# SCH_ESP-RotaryCell-Main-Carrier-Rev-A1_R.net
KiCad netlist of a schematic drawn in EasyEDA
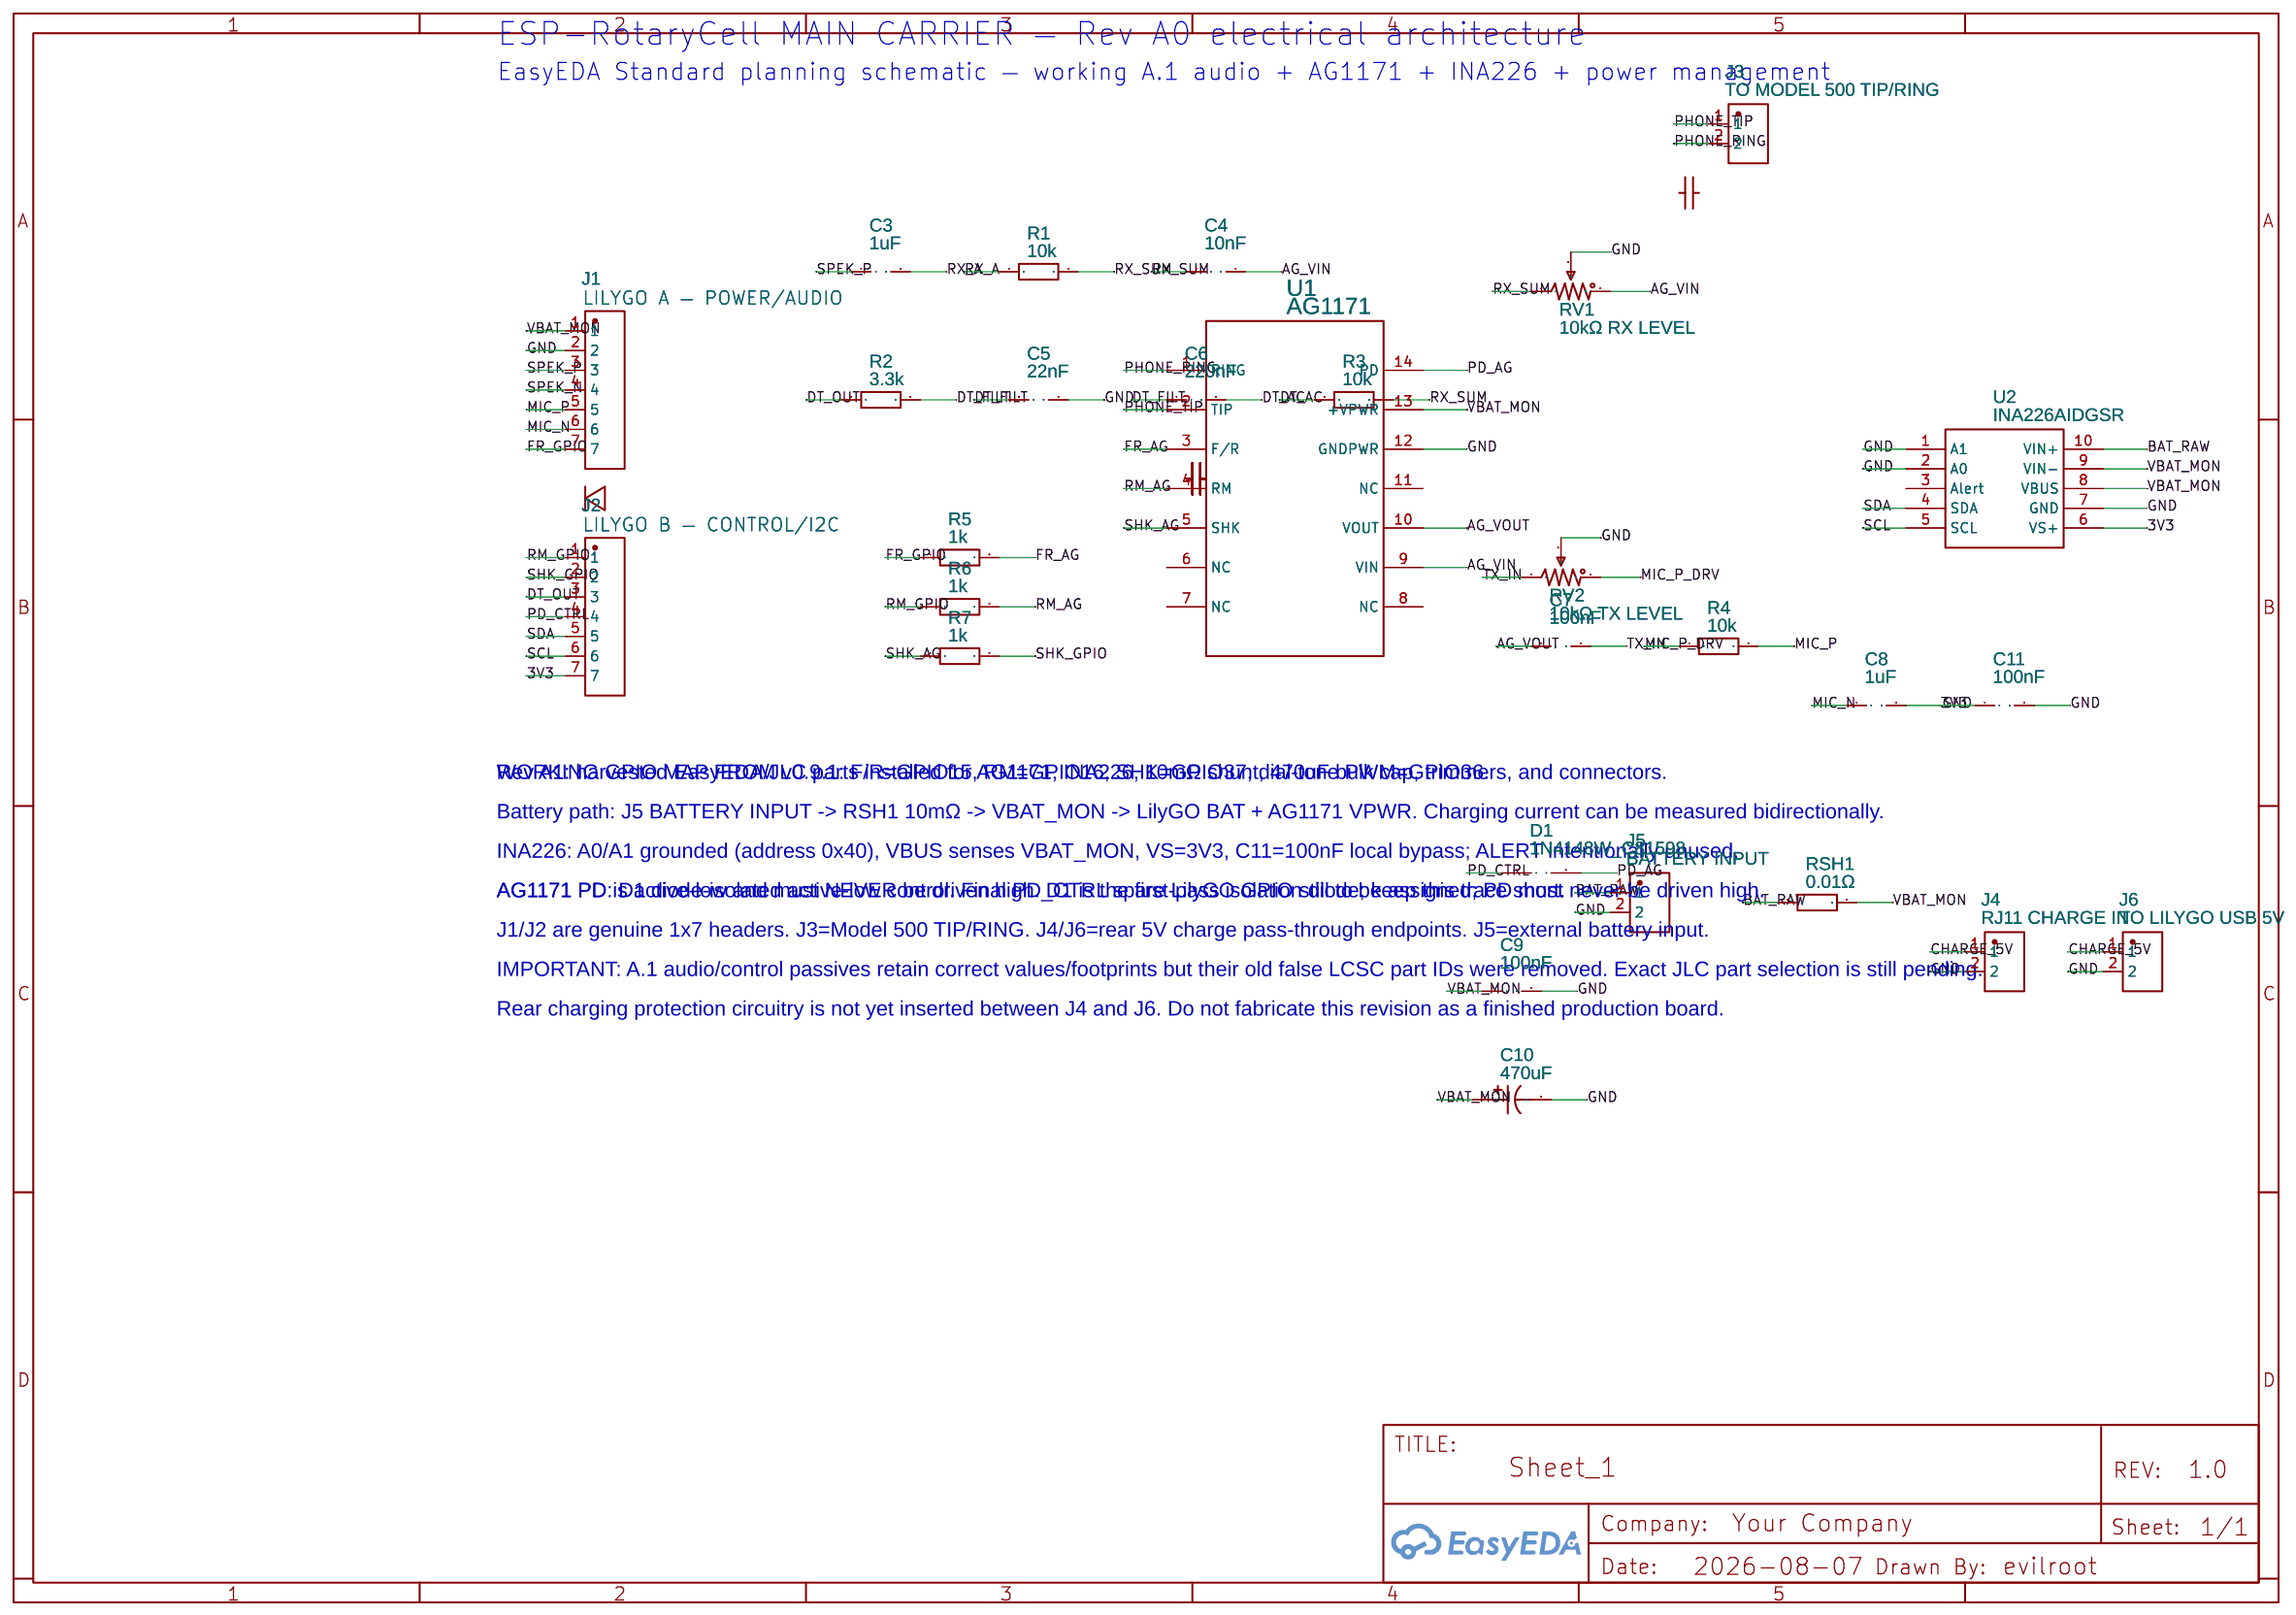
[diagram p0: Carrier_Rev_A1_RealParts]
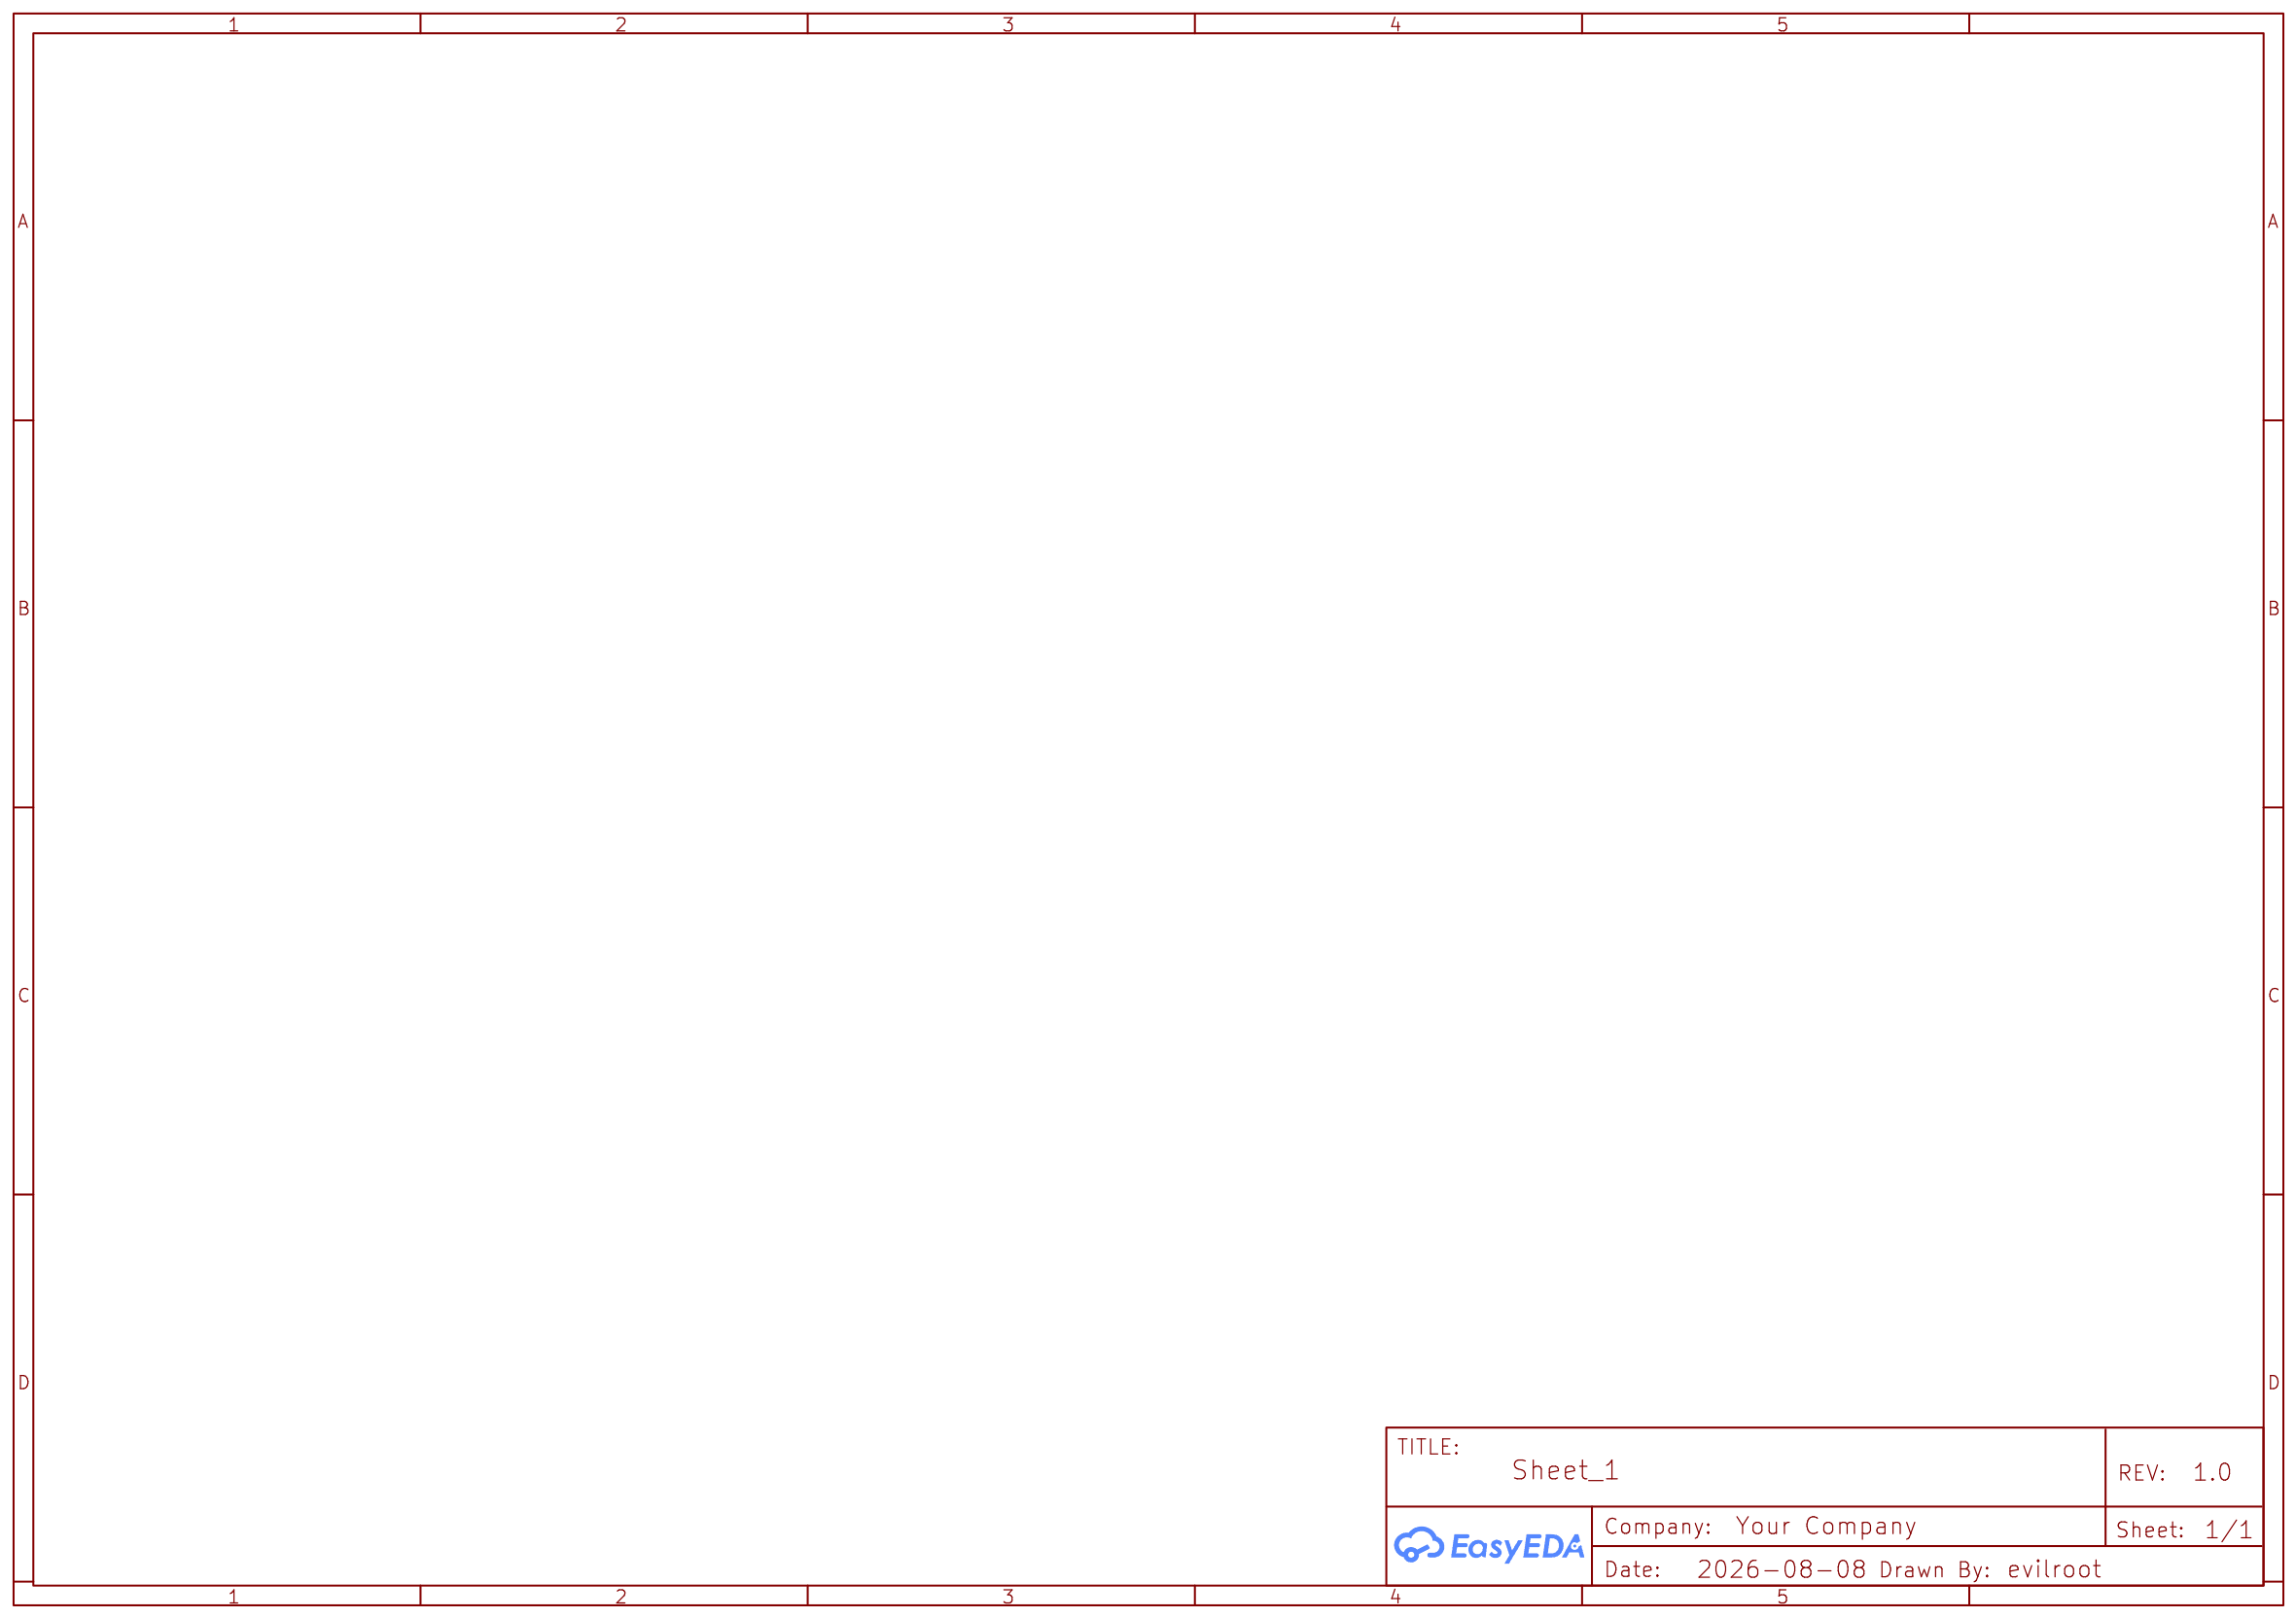
[diagram p1: Sheet_1]

(export (version "E")
  (design (tool "Eeschema 10.0.6"))
  (components
    (comp (ref "C3") (value "1uF") (libsource (lib "") (part "Unknown_440_-675")))
    (comp (ref "C4") (value "10nF") (libsource (lib "") (part "Unknown_610_-675")))
    (comp (ref "C5") (value "22nF") (libsource (lib "") (part "Unknown_520_-610")))
    (comp (ref "C6") (value "220nF") (libsource (lib "") (part "Unknown_600_-610")))
    (comp (ref "C7") (value "100nF") (libsource (lib "") (part "Unknown_785_-485")))
    (comp (ref "C8") (value "1uF") (libsource (lib "") (part "Unknown_945_-455")))
    (comp (ref "C9") (value "100nF") (libsource (lib "") (part "Unknown_760_-310")))
    (comp (ref "C10")
      (value "470uF")
      (fields
        (field (name "Manufacturer Part") "RYHT16V470UF5.5*11")
        (field (name "Manufacturer") "HONOR(荣誉)")
      )
      (libsource (lib "") (part "RYHT16V470UF5.5*11"))
    )
    (comp (ref "C11") (value "100nF") (libsource (lib "") (part "Unknown_1010_-455")))
    (comp (ref "D1")
      (value "1N4148W_C81598")
      (fields (field (name "Manufacturer Part") "1N4148W") (field (name "Manufacturer") "ST(先科)"))
      (libsource (lib "") (part "1N4148W_C81598"))
    )
    (comp (ref "J1")
      (value "LILYGO A — POWER/AUDIO")
      (fields
        (field (name "Manufacturer Part") "PM2.54-1x7PZZ-H8.5")
        (field (name "Manufacturer") "SHOU HAN(首韩)")
      )
      (libsource (lib "") (part "PM2.54-1X7PZZ-H8.5"))
    )
    (comp (ref "J2")
      (value "LILYGO B — CONTROL/I2C")
      (fields
        (field (name "Manufacturer Part") "PM2.54-1x7PZZ-H8.5")
        (field (name "Manufacturer") "SHOU HAN(首韩)")
      )
      (libsource (lib "") (part "PM2.54-1X7PZZ-H8.5"))
    )
    (comp (ref "J3")
      (value "TO MODEL 500 TIP/RING")
      (fields
        (field (name "Manufacturer Part") "HMT-2.54-1*2PM")
        (field (name "Manufacturer") "HMTCONN(华明通)")
      )
      (libsource (lib "") (part "HMT-2.54-1*2PM"))
    )
    (comp (ref "J4")
      (value "RJ11 CHARGE IN")
      (fields
        (field (name "Manufacturer Part") "HMT-2.54-1*2PM")
        (field (name "Manufacturer") "HMTCONN(华明通)")
      )
      (libsource (lib "") (part "HMT-2.54-1*2PM"))
    )
    (comp (ref "J5")
      (value "BATTERY INPUT")
      (fields
        (field (name "Manufacturer Part") "HMT-2.54-1*2PM")
        (field (name "Manufacturer") "HMTCONN(华明通)")
      )
      (libsource (lib "") (part "HMT-2.54-1*2PM"))
    )
    (comp (ref "J6")
      (value "TO LILYGO USB 5V")
      (fields
        (field (name "Manufacturer Part") "HMT-2.54-1*2PM")
        (field (name "Manufacturer") "HMTCONN(华明通)")
      )
      (libsource (lib "") (part "HMT-2.54-1*2PM"))
    )
    (comp (ref "R1") (value "10k") (libsource (lib "") (part "Unknown_520_-675")))
    (comp (ref "R2") (value "3.3k") (libsource (lib "") (part "Unknown_440_-610")))
    (comp (ref "R3") (value "10k") (libsource (lib "") (part "Unknown_680_-610")))
    (comp (ref "R4") (value "10k") (libsource (lib "") (part "Unknown_865_-485")))
    (comp (ref "R5") (value "1k") (libsource (lib "") (part "Unknown_480_-530")))
    (comp (ref "R6") (value "1k") (libsource (lib "") (part "Unknown_480_-505")))
    (comp (ref "R7") (value "1k") (libsource (lib "") (part "Unknown_480_-480")))
    (comp (ref "RSH1")
      (value "0.01Ω")
      (fields (field (name "Manufacturer Part") "MRF6432(2512)LR010JTS") (field (name "Manufacturer") "SUP"))
      (libsource (lib "") (part "MRF6432(2512)LR010JTS"))
    )
    (comp (ref "RV1")
      (value "10kΩ RX LEVEL")
      (fields (field (name "Manufacturer Part") "PS10KV50-103A3030") (field (name "Manufacturer") "Amphenol"))
      (libsource (lib "") (part "PS10KV50-103A3030"))
    )
    (comp (ref "RV2")
      (value "10kΩ TX LEVEL")
      (fields (field (name "Manufacturer Part") "PS10KV50-103A3030") (field (name "Manufacturer") "Amphenol"))
      (libsource (lib "") (part "PS10KV50-103A3030"))
    )
    (comp (ref "U1")
      (value "AG1171")
      (fields (field (name "Manufacturer Part") "Ag1171") (field (name "Manufacturer") "Silver Telecom"))
      (libsource (lib "") (part "AG1171"))
    )
    (comp (ref "U2")
      (value "INA226AIDGSR")
      (fields (field (name "Manufacturer") "TI(德州仪器)"))
      (libsource (lib "") (part "INA226AIDGSR"))
    )
  )
  (nets
    (net (code "1") (name "3V3") (class "Default")
      (node (ref "C10") (pin "2") (pinfunction "2_2") (pintype "input"))
      (node (ref "C11") (pin "1") (pinfunction "1_1") (pintype "input"))
      (node (ref "C11") (pin "2") (pinfunction "2_2") (pintype "input"))
      (node (ref "C5") (pin "2") (pinfunction "2_2") (pintype "input"))
      (node (ref "C8") (pin "2") (pinfunction "2_2") (pintype "input"))
      (node (ref "C9") (pin "2") (pinfunction "2_2") (pintype "input"))
      (node (ref "J1") (pin "2") (pinfunction "2_2") (pintype "unspecified"))
      (node (ref "J2") (pin "7") (pinfunction "7_7") (pintype "unspecified"))
      (node (ref "J4") (pin "2") (pinfunction "2_2") (pintype "unspecified"))
      (node (ref "J5") (pin "2") (pinfunction "2_2") (pintype "unspecified"))
      (node (ref "J6") (pin "2") (pinfunction "2_2") (pintype "unspecified"))
      (node (ref "RV1") (pin "3") (pinfunction "3_3") (pintype "unspecified"))
      (node (ref "RV2") (pin "3") (pinfunction "3_3") (pintype "unspecified"))
      (node (ref "U1") (pin "12") (pinfunction "GNDPWR_12") (pintype "unspecified"))
      (node (ref "U2") (pin "1") (pinfunction "A1_1") (pintype "unspecified"))
      (node (ref "U2") (pin "2") (pinfunction "A0_2") (pintype "unspecified"))
      (node (ref "U2") (pin "6") (pinfunction "VS+_6") (pintype "unspecified"))
      (node (ref "U2") (pin "7") (pinfunction "GND_7") (pintype "unspecified"))
    )
    (net (code "2") (name "AG_VIN") (class "Default")
      (node (ref "C4") (pin "2") (pinfunction "2_2") (pintype "input"))
      (node (ref "RV1") (pin "2") (pinfunction "2_2") (pintype "unspecified"))
      (node (ref "U1") (pin "9") (pinfunction "VIN_9") (pintype "unspecified"))
    )
    (net (code "3") (name "AG_VOUT") (class "Default")
      (node (ref "C7") (pin "1") (pinfunction "1_1") (pintype "input"))
      (node (ref "U1") (pin "10") (pinfunction "VOUT_10") (pintype "unspecified"))
    )
    (net (code "4") (name "BAT_RAW") (class "Default")
      (node (ref "J5") (pin "1") (pinfunction "1_1") (pintype "unspecified"))
      (node (ref "RSH1") (pin "1") (pinfunction "1_1") (pintype "input"))
      (node (ref "U2") (pin "10") (pinfunction "VIN+_10") (pintype "unspecified"))
    )
    (net (code "5") (name "CHARGE_5V") (class "Default")
      (node (ref "J4") (pin "1") (pinfunction "1_1") (pintype "unspecified"))
      (node (ref "J6") (pin "1") (pinfunction "1_1") (pintype "unspecified"))
    )
    (net (code "6") (name "DT_AC") (class "Default")
      (node (ref "C6") (pin "2") (pinfunction "2_2") (pintype "input"))
      (node (ref "R3") (pin "1") (pinfunction "1_1") (pintype "input"))
    )
    (net (code "7") (name "DT_FILT") (class "Default")
      (node (ref "C5") (pin "1") (pinfunction "1_1") (pintype "input"))
      (node (ref "C6") (pin "1") (pinfunction "1_1") (pintype "input"))
      (node (ref "R2") (pin "2") (pinfunction "2_2") (pintype "input"))
    )
    (net (code "8") (name "DT_OUT") (class "Default")
      (node (ref "J2") (pin "3") (pinfunction "3_3") (pintype "unspecified"))
      (node (ref "R2") (pin "1") (pinfunction "1_1") (pintype "input"))
    )
    (net (code "9") (name "FR_AG") (class "Default")
      (node (ref "R5") (pin "2") (pinfunction "2_2") (pintype "input"))
      (node (ref "U1") (pin "3") (pinfunction "F/R_3") (pintype "unspecified"))
    )
    (net (code "10") (name "FR_GPIO") (class "Default")
      (node (ref "J1") (pin "7") (pinfunction "7_7") (pintype "unspecified"))
      (node (ref "R5") (pin "1") (pinfunction "1_1") (pintype "input"))
    )
    (net (code "11") (name "MIC_N") (class "Default")
      (node (ref "C8") (pin "1") (pinfunction "1_1") (pintype "input"))
      (node (ref "J1") (pin "6") (pinfunction "6_6") (pintype "unspecified"))
    )
    (net (code "12") (name "MIC_P") (class "Default")
      (node (ref "J1") (pin "5") (pinfunction "5_5") (pintype "unspecified"))
      (node (ref "R4") (pin "2") (pinfunction "2_2") (pintype "input"))
    )
    (net (code "13") (name "MIC_P_DRV") (class "Default")
      (node (ref "R4") (pin "1") (pinfunction "1_1") (pintype "input"))
      (node (ref "RV2") (pin "2") (pinfunction "2_2") (pintype "unspecified"))
    )
    (net (code "14") (name "PD_AG") (class "Default")
      (node (ref "D1") (pin "2") (pinfunction "A_2") (pintype "unspecified"))
      (node (ref "U1") (pin "14") (pinfunction "PD_14") (pintype "unspecified"))
    )
    (net (code "15") (name "PD_CTRL") (class "Default")
      (node (ref "D1") (pin "1") (pinfunction "K_1") (pintype "unspecified"))
      (node (ref "J2") (pin "4") (pinfunction "4_4") (pintype "unspecified"))
    )
    (net (code "16") (name "PHONE_RING") (class "Default")
      (node (ref "J3") (pin "2") (pinfunction "2_2") (pintype "unspecified"))
      (node (ref "U1") (pin "1") (pinfunction "RING_1") (pintype "unspecified"))
    )
    (net (code "17") (name "PHONE_TIP") (class "Default")
      (node (ref "J3") (pin "1") (pinfunction "1_1") (pintype "unspecified"))
      (node (ref "U1") (pin "2") (pinfunction "TIP_2") (pintype "unspecified"))
    )
    (net (code "18") (name "RM_AG") (class "Default")
      (node (ref "R6") (pin "2") (pinfunction "2_2") (pintype "input"))
      (node (ref "U1") (pin "4") (pinfunction "RM_4") (pintype "unspecified"))
    )
    (net (code "19") (name "RM_GPIO") (class "Default")
      (node (ref "J2") (pin "1") (pinfunction "1_1") (pintype "unspecified"))
      (node (ref "R6") (pin "1") (pinfunction "1_1") (pintype "input"))
    )
    (net (code "20") (name "RX_A") (class "Default")
      (node (ref "C3") (pin "2") (pinfunction "2_2") (pintype "input"))
      (node (ref "R1") (pin "1") (pinfunction "1_1") (pintype "input"))
    )
    (net (code "21") (name "RX_SUM") (class "Default")
      (node (ref "C4") (pin "1") (pinfunction "1_1") (pintype "input"))
      (node (ref "R1") (pin "2") (pinfunction "2_2") (pintype "input"))
      (node (ref "R3") (pin "2") (pinfunction "2_2") (pintype "input"))
      (node (ref "RV1") (pin "1") (pinfunction "1_1") (pintype "unspecified"))
    )
    (net (code "22") (name "SCL") (class "Default")
      (node (ref "J2") (pin "6") (pinfunction "6_6") (pintype "unspecified"))
      (node (ref "U2") (pin "5") (pinfunction "SCL_5") (pintype "unspecified"))
    )
    (net (code "23") (name "SDA") (class "Default")
      (node (ref "J2") (pin "5") (pinfunction "5_5") (pintype "unspecified"))
      (node (ref "U2") (pin "4") (pinfunction "SDA_4") (pintype "unspecified"))
    )
    (net (code "24") (name "SHK_AG") (class "Default")
      (node (ref "R7") (pin "1") (pinfunction "1_1") (pintype "input"))
      (node (ref "U1") (pin "5") (pinfunction "SHK_5") (pintype "unspecified"))
    )
    (net (code "25") (name "SHK_GPIO") (class "Default")
      (node (ref "J2") (pin "2") (pinfunction "2_2") (pintype "unspecified"))
      (node (ref "R7") (pin "2") (pinfunction "2_2") (pintype "input"))
    )
    (net (code "26") (name "SPEK_N") (class "Default")
      (node (ref "J1") (pin "4") (pinfunction "4_4") (pintype "unspecified"))
    )
    (net (code "27") (name "SPEK_P") (class "Default")
      (node (ref "C3") (pin "1") (pinfunction "1_1") (pintype "input"))
      (node (ref "J1") (pin "3") (pinfunction "3_3") (pintype "unspecified"))
    )
    (net (code "28") (name "TX_IN") (class "Default")
      (node (ref "C7") (pin "2") (pinfunction "2_2") (pintype "input"))
      (node (ref "RV2") (pin "1") (pinfunction "1_1") (pintype "unspecified"))
    )
    (net (code "29") (name "VBAT_MON") (class "Default")
      (node (ref "C10") (pin "1") (pinfunction "1_1") (pintype "input"))
      (node (ref "C9") (pin "1") (pinfunction "1_1") (pintype "input"))
      (node (ref "J1") (pin "1") (pinfunction "1_1") (pintype "unspecified"))
      (node (ref "RSH1") (pin "2") (pinfunction "2_2") (pintype "input"))
      (node (ref "U1") (pin "13") (pinfunction "+VPWR_13") (pintype "unspecified"))
      (node (ref "U2") (pin "8") (pinfunction "VBUS_8") (pintype "unspecified"))
      (node (ref "U2") (pin "9") (pinfunction "VIN-_9") (pintype "unspecified"))
    )
    (net (code "30") (name "unconnected-(U1-NC-Pad6)") (class "Default")
      (node (ref "U1") (pin "6") (pinfunction "NC_6") (pintype "unspecified"))
    )
    (net (code "31") (name "unconnected-(U1-NC-Pad7)") (class "Default")
      (node (ref "U1") (pin "7") (pinfunction "NC_7") (pintype "unspecified"))
    )
    (net (code "32") (name "unconnected-(U1-NC-Pad8)") (class "Default")
      (node (ref "U1") (pin "8") (pinfunction "NC_8") (pintype "unspecified"))
    )
    (net (code "33") (name "unconnected-(U1-NC-Pad11)") (class "Default")
      (node (ref "U1") (pin "11") (pinfunction "NC_11") (pintype "unspecified"))
    )
    (net (code "34") (name "unconnected-(U2-Alert-Pad3)") (class "Default")
      (node (ref "U2") (pin "3") (pinfunction "Alert_3") (pintype "unspecified"))
    )
  )
)
